# Open_Lamborghino.net
KiCad netlist of a schematic drawn in Altium Designer
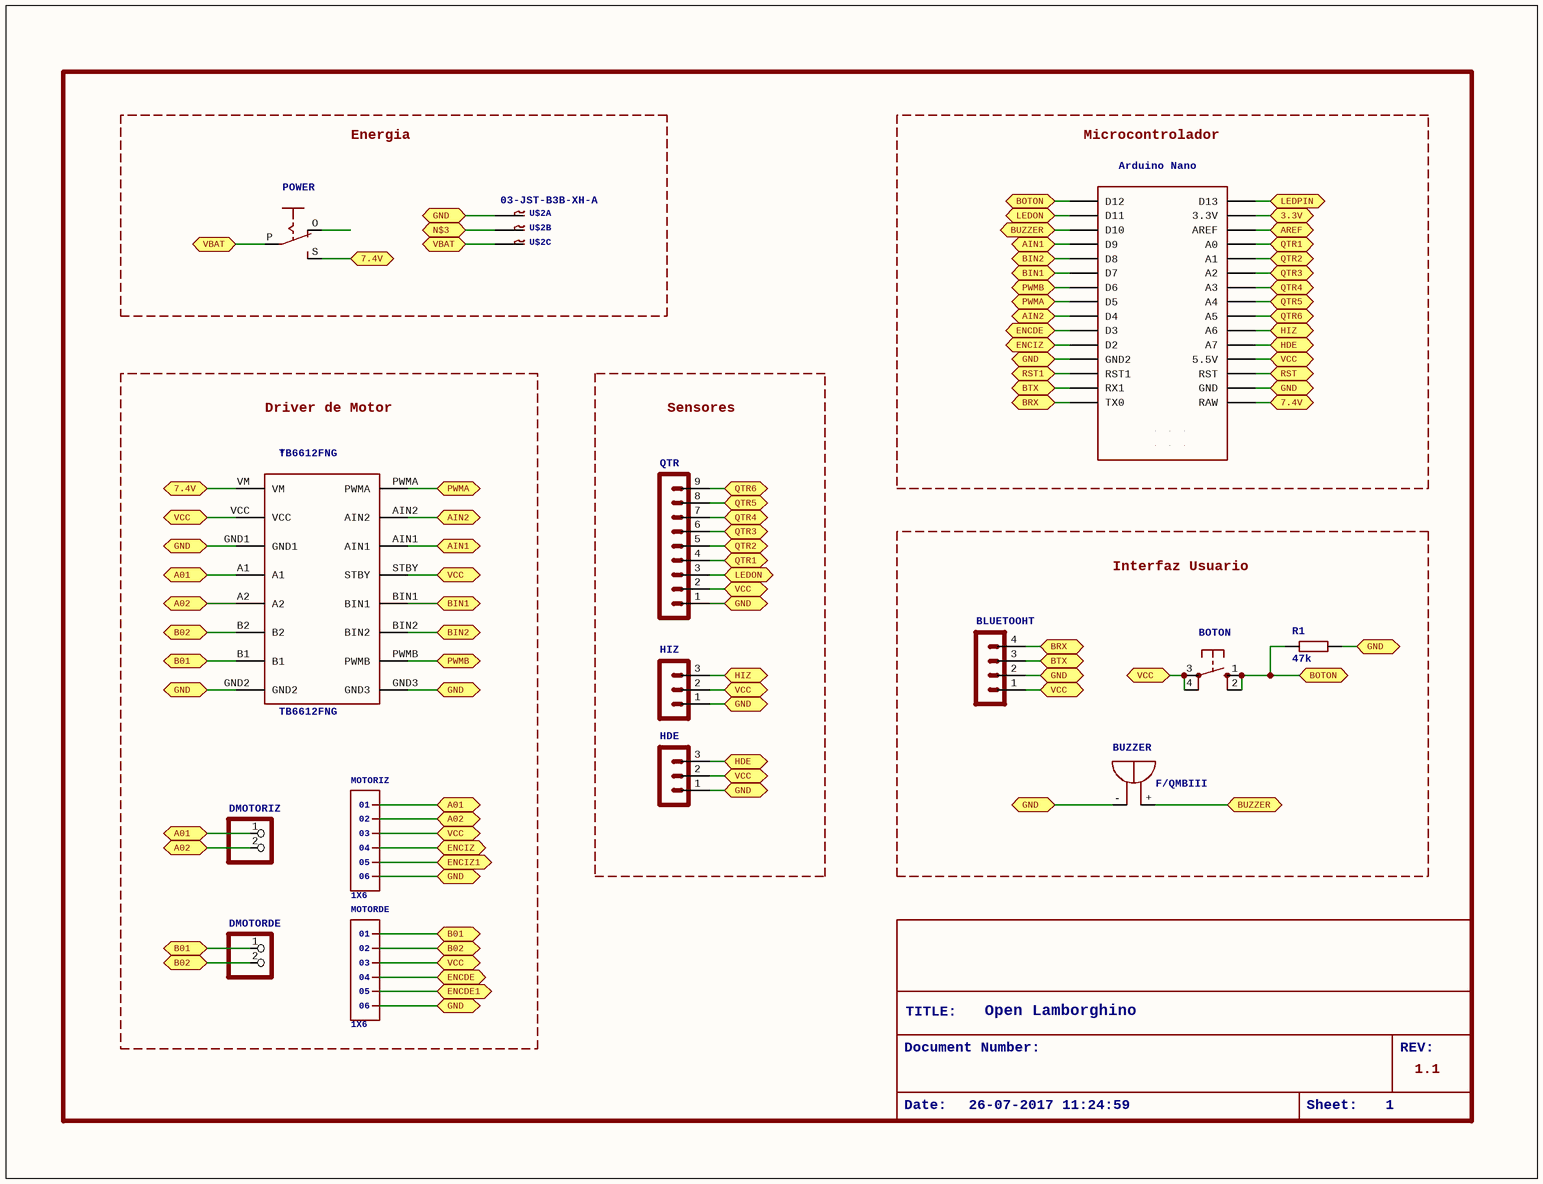
[diagram p0: Open Lamborghino.SchDoc]

(export (version "E")
  (design (tool "Eeschema 10.0.6"))
  (components
    (comp (ref "BLUETOOHT")
      (value "MA04-1")
      (footprint "MA04-1")
      (description "PIN HEADER")
      (libsource (lib "con-lstb") (part "MA04-1"))
    )
    (comp (ref "BOTON")
      (value "10-XX")
      (footprint "B3F-10XX")
      (description "OMRON SWITCH")
      (fields (field (name "MPN") "B3F-1000"))
      (libsource (lib "switch-omron") (part "10-XX"))
    )
    (comp (ref "BUZZER")
      (value "F/QMBIII")
      (footprint "F/QMBIII")
      (description "BUZZER    Source: Buerklin")
      (libsource (lib "buzzer") (part "F/QMBIII"))
    )
    (comp (ref "DMOTORDE")
      (value "PINHD-1X2")
      (footprint "1X02")
      (description "PIN HEADER")
      (libsource (lib "pinhead") (part "PINHD-1X2"))
    )
    (comp (ref "DMOTORIZ")
      (value "PINHD-1X2")
      (footprint "1X02")
      (description "PIN HEADER")
      (libsource (lib "pinhead") (part "PINHD-1X2"))
    )
    (comp (ref "HDE")
      (value "MA03-1")
      (footprint "MA03-1")
      (description "PIN HEADER")
      (libsource (lib "con-lstb") (part "MA03-1"))
    )
    (comp (ref "HIZ")
      (value "MA03-1")
      (footprint "MA03-1")
      (description "PIN HEADER")
      (libsource (lib "con-lstb") (part "MA03-1"))
    )
    (comp (ref "MOTORDE")
      (value "1X6")
      (footprint "1X6")
      (fields
        (field (name "01") "01")
        (field (name "02") "02")
        (field (name "03") "03")
        (field (name "04") "04")
        (field (name "05") "05")
        (field (name "06") "06")
      )
      (libsource (lib "headers(2mm)(samtec)") (part "1X6"))
    )
    (comp (ref "MOTORIZ")
      (value "1X6")
      (footprint "1X6")
      (fields
        (field (name "01") "01")
        (field (name "02") "02")
        (field (name "03") "03")
        (field (name "04") "04")
        (field (name "05") "05")
        (field (name "06") "06")
      )
      (libsource (lib "headers(2mm)(samtec)") (part "1X6"))
    )
    (comp (ref "POWER") (value "EG1218S") (footprint "EG1218") (libsource (lib "adafruit") (part "EG1218S")))
    (comp (ref "QTR")
      (value "MA09-1")
      (footprint "MA09-1")
      (description "PIN HEADER")
      (libsource (lib "con-lstb") (part "MA09-1"))
    )
    (comp (ref "R1")
      (value "47k")
      (footprint "R1206")
      (description "RESISTOR, European symbol")
      (libsource (lib "rcl") (part "R-EU_R1206"))
    )
    (comp (ref "TB6612FNG")
      (value "TB6612FNG")
      (footprint "TB6612FNG")
      (fields (field (name "NAME") "*"))
      (libsource (lib "TB6612FNG") (part "TB6612FNG"))
    )
    (comp (ref "U$1")
      (value "NANO")
      (footprint "NANO")
      (description "Arduino Nano")
      (fields (field (name "ARDUINONANO") "Arduino Nano"))
      (libsource (lib "Arduino") (part "NANO"))
    )
    (comp (ref "U$2")
      (value "03-JST-B3B-XH-A")
      (footprint "B3B-XH")
      (description "JST CONNECTOR")
      (libsource (lib "jst") (part "03-JST-B3B-XH-A"))
    )
  )
  (nets
    (net (code "1") (name "/3.3V") (class "Default")
      (node (ref "U$1") (pin "3.3V") (pinfunction "3.3V_3.3V") (pintype "passive"))
    )
    (net (code "2") (name "/7.4V") (class "Default")
      (node (ref "POWER") (pin "S") (pinfunction "S_S") (pintype "passive"))
      (node (ref "TB6612FNG") (pin "VM") (pinfunction "VM_VM") (pintype "passive"))
      (node (ref "U$1") (pin "RAW") (pinfunction "RAW_RAW") (pintype "passive"))
    )
    (net (code "3") (name "/A01") (class "Default")
      (node (ref "DMOTORIZ") (pin "1") (pinfunction "1_1") (pintype "passive"))
      (node (ref "MOTORIZ") (pin "1") (pinfunction "1_1") (pintype "passive"))
      (node (ref "TB6612FNG") (pin "A1") (pinfunction "A1_A1") (pintype "passive"))
    )
    (net (code "4") (name "/A02") (class "Default")
      (node (ref "DMOTORIZ") (pin "2") (pinfunction "2_2") (pintype "passive"))
      (node (ref "MOTORIZ") (pin "2") (pinfunction "2_2") (pintype "passive"))
      (node (ref "TB6612FNG") (pin "A2") (pinfunction "A2_A2") (pintype "passive"))
    )
    (net (code "5") (name "/AIN1") (class "Default")
      (node (ref "TB6612FNG") (pin "AIN1") (pinfunction "AIN1_AIN1") (pintype "passive"))
      (node (ref "U$1") (pin "D9") (pinfunction "D9_D9") (pintype "passive"))
    )
    (net (code "6") (name "/AIN2") (class "Default")
      (node (ref "TB6612FNG") (pin "AIN2") (pinfunction "AIN2_AIN2") (pintype "passive"))
      (node (ref "U$1") (pin "D4") (pinfunction "D4_D4") (pintype "passive"))
    )
    (net (code "7") (name "/AREF") (class "Default")
      (node (ref "U$1") (pin "AREF") (pinfunction "AREF_AREF") (pintype "passive"))
    )
    (net (code "8") (name "/B01") (class "Default")
      (node (ref "DMOTORDE") (pin "1") (pinfunction "1_1") (pintype "passive"))
      (node (ref "MOTORDE") (pin "1") (pinfunction "1_1") (pintype "passive"))
      (node (ref "TB6612FNG") (pin "B1") (pinfunction "B1_B1") (pintype "passive"))
    )
    (net (code "9") (name "/B02") (class "Default")
      (node (ref "DMOTORDE") (pin "2") (pinfunction "2_2") (pintype "passive"))
      (node (ref "MOTORDE") (pin "2") (pinfunction "2_2") (pintype "passive"))
      (node (ref "TB6612FNG") (pin "B2") (pinfunction "B2_B2") (pintype "passive"))
    )
    (net (code "10") (name "/BIN1") (class "Default")
      (node (ref "TB6612FNG") (pin "BIN1") (pinfunction "BIN1_BIN1") (pintype "passive"))
      (node (ref "U$1") (pin "D7") (pinfunction "D7_D7") (pintype "passive"))
    )
    (net (code "11") (name "/BIN2") (class "Default")
      (node (ref "TB6612FNG") (pin "BIN2") (pinfunction "BIN2_BIN2") (pintype "passive"))
      (node (ref "U$1") (pin "D8") (pinfunction "D8_D8") (pintype "passive"))
    )
    (net (code "12") (name "/BOTON") (class "Default")
      (node (ref "BOTON") (pin "1") (pinfunction "S_1") (pintype "passive"))
      (node (ref "BOTON") (pin "2") (pinfunction "S1_2") (pintype "passive"))
      (node (ref "R1") (pin "1") (pinfunction "1_1") (pintype "passive"))
      (node (ref "U$1") (pin "D12") (pinfunction "D12_D12") (pintype "passive"))
    )
    (net (code "13") (name "/BRX") (class "Default")
      (node (ref "BLUETOOHT") (pin "4") (pinfunction "4_4") (pintype "passive"))
      (node (ref "U$1") (pin "TX0") (pinfunction "TX0_TX0") (pintype "passive"))
    )
    (net (code "14") (name "/BTX") (class "Default")
      (node (ref "BLUETOOHT") (pin "3") (pinfunction "3_3") (pintype "passive"))
      (node (ref "U$1") (pin "RX1") (pinfunction "RX1_RX1") (pintype "passive"))
    )
    (net (code "15") (name "/BUZZER") (class "Default")
      (node (ref "BUZZER") (pin "+") (pinfunction "-_+") (pintype "passive"))
      (node (ref "U$1") (pin "D10") (pinfunction "D10_D10") (pintype "passive"))
    )
    (net (code "16") (name "/ENCDE") (class "Default")
      (node (ref "MOTORDE") (pin "4") (pinfunction "4_4") (pintype "passive"))
      (node (ref "U$1") (pin "D3") (pinfunction "D3_D3") (pintype "passive"))
    )
    (net (code "17") (name "/ENCDE1") (class "Default")
      (node (ref "MOTORDE") (pin "5") (pinfunction "5_5") (pintype "passive"))
    )
    (net (code "18") (name "/ENCIZ") (class "Default")
      (node (ref "MOTORIZ") (pin "4") (pinfunction "4_4") (pintype "passive"))
      (node (ref "U$1") (pin "D2") (pinfunction "D2_D2") (pintype "passive"))
    )
    (net (code "19") (name "/ENCIZ1") (class "Default")
      (node (ref "MOTORIZ") (pin "5") (pinfunction "5_5") (pintype "passive"))
    )
    (net (code "20") (name "/GND") (class "Default")
      (node (ref "BLUETOOHT") (pin "2") (pinfunction "2_2") (pintype "passive"))
      (node (ref "BUZZER") (pin "-") (pinfunction "+_-") (pintype "passive"))
      (node (ref "HDE") (pin "1") (pinfunction "1_1") (pintype "passive"))
      (node (ref "HIZ") (pin "1") (pinfunction "1_1") (pintype "passive"))
      (node (ref "MOTORDE") (pin "6") (pinfunction "6_6") (pintype "passive"))
      (node (ref "MOTORIZ") (pin "6") (pinfunction "6_6") (pintype "passive"))
      (node (ref "QTR") (pin "1") (pinfunction "1_1") (pintype "passive"))
      (node (ref "R1") (pin "2") (pinfunction "2_2") (pintype "passive"))
      (node (ref "TB6612FNG") (pin "GND1") (pinfunction "GND1_GND1") (pintype "passive"))
      (node (ref "TB6612FNG") (pin "GND2") (pinfunction "GND2_GND2") (pintype "passive"))
      (node (ref "TB6612FNG") (pin "GND3") (pinfunction "GND3_GND3") (pintype "passive"))
      (node (ref "U$1") (pin "GND") (pinfunction "GND_GND") (pintype "passive"))
      (node (ref "U$1") (pin "GND1") (pinfunction "GND2_GND1") (pintype "passive"))
      (node (ref "U$2") (pin "P$1") (pinfunction "1_P$1") (pintype "passive"))
    )
    (net (code "21") (name "/HDE") (class "Default")
      (node (ref "HDE") (pin "3") (pinfunction "3_3") (pintype "passive"))
      (node (ref "U$1") (pin "A7") (pinfunction "A7_A7") (pintype "passive"))
    )
    (net (code "22") (name "/HIZ") (class "Default")
      (node (ref "HIZ") (pin "3") (pinfunction "3_3") (pintype "passive"))
      (node (ref "U$1") (pin "A6") (pinfunction "A6_A6") (pintype "passive"))
    )
    (net (code "23") (name "/LEDON") (class "Default")
      (node (ref "QTR") (pin "3") (pinfunction "3_3") (pintype "passive"))
      (node (ref "U$1") (pin "D11") (pinfunction "D11_D11") (pintype "passive"))
    )
    (net (code "24") (name "/LEDPIN") (class "Default")
      (node (ref "U$1") (pin "D13") (pinfunction "D13_D13") (pintype "passive"))
    )
    (net (code "25") (name "/N$3") (class "Default")
      (node (ref "U$2") (pin "P$2") (pinfunction "1_P$2") (pintype "passive"))
    )
    (net (code "26") (name "/PWMA") (class "Default")
      (node (ref "TB6612FNG") (pin "PWMA") (pinfunction "PWMA_PWMA") (pintype "passive"))
      (node (ref "U$1") (pin "D5") (pinfunction "D5_D5") (pintype "passive"))
    )
    (net (code "27") (name "/PWMB") (class "Default")
      (node (ref "TB6612FNG") (pin "PWMB") (pinfunction "PWMB_PWMB") (pintype "passive"))
      (node (ref "U$1") (pin "D6") (pinfunction "D6_D6") (pintype "passive"))
    )
    (net (code "28") (name "/QTR1") (class "Default")
      (node (ref "QTR") (pin "4") (pinfunction "4_4") (pintype "passive"))
      (node (ref "U$1") (pin "A0") (pinfunction "A0_A0") (pintype "passive"))
    )
    (net (code "29") (name "/QTR2") (class "Default")
      (node (ref "QTR") (pin "5") (pinfunction "5_5") (pintype "passive"))
      (node (ref "U$1") (pin "A1") (pinfunction "A1_A1") (pintype "passive"))
    )
    (net (code "30") (name "/QTR3") (class "Default")
      (node (ref "QTR") (pin "6") (pinfunction "6_6") (pintype "passive"))
      (node (ref "U$1") (pin "A2") (pinfunction "A2_A2") (pintype "passive"))
    )
    (net (code "31") (name "/QTR4") (class "Default")
      (node (ref "QTR") (pin "7") (pinfunction "7_7") (pintype "passive"))
      (node (ref "U$1") (pin "A3") (pinfunction "A3_A3") (pintype "passive"))
    )
    (net (code "32") (name "/QTR5") (class "Default")
      (node (ref "QTR") (pin "8") (pinfunction "8_8") (pintype "passive"))
      (node (ref "U$1") (pin "A4") (pinfunction "A4_A4") (pintype "passive"))
    )
    (net (code "33") (name "/QTR6") (class "Default")
      (node (ref "QTR") (pin "9") (pinfunction "9_9") (pintype "passive"))
      (node (ref "U$1") (pin "A5") (pinfunction "A5_A5") (pintype "passive"))
    )
    (net (code "34") (name "/RST") (class "Default")
      (node (ref "U$1") (pin "RST") (pinfunction "RST_RST") (pintype "passive"))
    )
    (net (code "35") (name "/RST1") (class "Default")
      (node (ref "U$1") (pin "RST1") (pinfunction "RST1_RST1") (pintype "passive"))
    )
    (net (code "36") (name "/VBAT") (class "Default")
      (node (ref "POWER") (pin "P") (pinfunction "P_P") (pintype "passive"))
      (node (ref "U$2") (pin "P$3") (pinfunction "1_P$3") (pintype "passive"))
    )
    (net (code "37") (name "/VCC") (class "Default")
      (node (ref "BLUETOOHT") (pin "1") (pinfunction "1_1") (pintype "passive"))
      (node (ref "BOTON") (pin "3") (pinfunction "P_3") (pintype "passive"))
      (node (ref "BOTON") (pin "4") (pinfunction "P1_4") (pintype "passive"))
      (node (ref "HDE") (pin "2") (pinfunction "2_2") (pintype "passive"))
      (node (ref "HIZ") (pin "2") (pinfunction "2_2") (pintype "passive"))
      (node (ref "MOTORDE") (pin "3") (pinfunction "3_3") (pintype "passive"))
      (node (ref "MOTORIZ") (pin "3") (pinfunction "3_3") (pintype "passive"))
      (node (ref "QTR") (pin "2") (pinfunction "2_2") (pintype "passive"))
      (node (ref "TB6612FNG") (pin "STBY") (pinfunction "STBY_STBY") (pintype "passive"))
      (node (ref "TB6612FNG") (pin "VCC") (pinfunction "VCC_VCC") (pintype "passive"))
      (node (ref "U$1") (pin "5V") (pinfunction "5.5V_5V") (pintype "passive"))
    )
    (net (code "38") (name "unconnected-(POWER-PadO)") (class "Default")
      (node (ref "POWER") (pin "O") (pinfunction "O_O") (pintype "passive"))
    )
    (net (code "39") (name "unconnected-(U$1-PadICSP1)") (class "Default")
      (node (ref "U$1") (pin "ICSP1") (pinfunction "ICSP1_ICSP1") (pintype "passive"))
    )
    (net (code "40") (name "unconnected-(U$1-PadICSP2)") (class "Default")
      (node (ref "U$1") (pin "ICSP2") (pinfunction "ICSP2_ICSP2") (pintype "passive"))
    )
    (net (code "41") (name "unconnected-(U$1-PadICSP3)") (class "Default")
      (node (ref "U$1") (pin "ICSP3") (pinfunction "ICSP3_ICSP3") (pintype "passive"))
    )
    (net (code "42") (name "unconnected-(U$1-PadICSP4)") (class "Default")
      (node (ref "U$1") (pin "ICSP4") (pinfunction "ICSP4_ICSP4") (pintype "passive"))
    )
    (net (code "43") (name "unconnected-(U$1-PadICSP5)") (class "Default")
      (node (ref "U$1") (pin "ICSP5") (pinfunction "ICSP5_ICSP5") (pintype "passive"))
    )
    (net (code "44") (name "unconnected-(U$1-PadICSP6)") (class "Default")
      (node (ref "U$1") (pin "ICSP6") (pinfunction "ICSP6_ICSP6") (pintype "passive"))
    )
  )
)
